# Schematic.net
KiCad netlist of a schematic drawn in Altium Designer
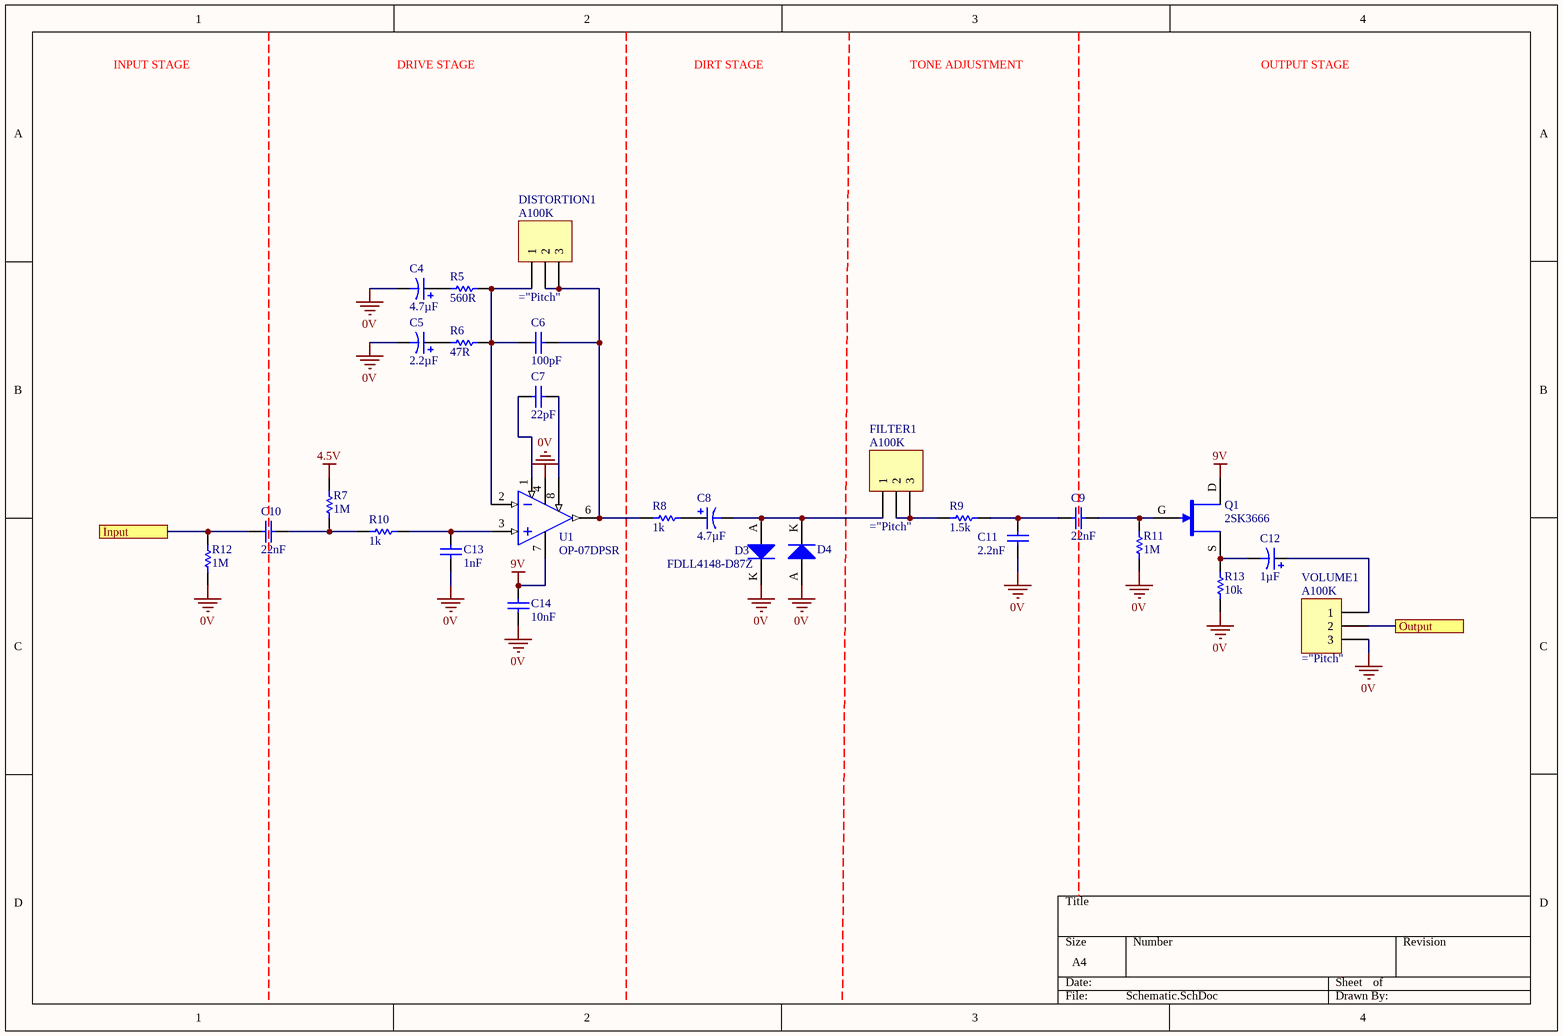
[diagram p0: Schematic.SchDoc]

(export (version "E")
  (design (tool "Eeschema 10.0.6"))
  (components
    (comp (ref "C4")
      (value "~")
      (footprint "1206")
      (fields
        (field (name "PART NUMBER") "TAJA475K025RNJ")
        (field (name "TOLERANCE") "±10%")
        (field (name "MANUFACTURER") "AVX Corporation")
      )
      (libsource (lib "ts_20-standard-library") (part "Capacitor (Polarised)"))
    )
    (comp (ref "C5")
      (value "~")
      (footprint "1206")
      (fields
        (field (name "PART NUMBER") "TAJA225K025RNJ")
        (field (name "TOLERANCE") "±10%")
        (field (name "MANUFACTURER") "AVX Corporation")
      )
      (libsource (lib "ts_20-standard-library") (part "Capacitor (Polarised)"))
    )
    (comp (ref "C6")
      (value "100pF")
      (footprint "0805")
      (fields
        (field (name "PART NUMBER") "GCM2165C1H101JA16D")
        (field (name "TOLERANCE") "±5%")
        (field (name "MANUFACTURER") "muRata")
      )
      (libsource (lib "ts_20-standard-library") (part "Capacitor"))
    )
    (comp (ref "C7")
      (value "22pF")
      (footprint "0805")
      (fields
        (field (name "PART NUMBER") "GRM21A5C2E220JW01D")
        (field (name "TOLERANCE") "±5%")
        (field (name "MANUFACTURER") "muRata")
      )
      (libsource (lib "ts_20-standard-library") (part "Capacitor"))
    )
    (comp (ref "C8")
      (value "~")
      (footprint "1206")
      (fields
        (field (name "PART NUMBER") "TAJA475K025RNJ")
        (field (name "TOLERANCE") "±10%")
        (field (name "MANUFACTURER") "AVX Corporation")
      )
      (libsource (lib "ts_20-standard-library") (part "Capacitor (Polarised)"))
    )
    (comp (ref "C9")
      (value "22nF")
      (footprint "0805")
      (fields
        (field (name "PART NUMBER") "GCM21B5C1H223JA16L")
        (field (name "TOLERANCE") "±5%")
        (field (name "MANUFACTURER") "muRata")
      )
      (libsource (lib "ts_20-standard-library") (part "Capacitor"))
    )
    (comp (ref "C10")
      (value "22nF")
      (footprint "0805")
      (fields
        (field (name "PART NUMBER") "GCM21B5C1H223JA16L")
        (field (name "TOLERANCE") "±5%")
        (field (name "MANUFACTURER") "muRata")
      )
      (libsource (lib "ts_20-standard-library") (part "Capacitor"))
    )
    (comp (ref "C11")
      (value "2.2nF")
      (footprint "0805")
      (fields
        (field (name "PART NUMBER") "GCM2165C1H222JA16D")
        (field (name "TOLERANCE") "±5%")
        (field (name "MANUFACTURER") "muRata")
      )
      (libsource (lib "ts_20-standard-library") (part "Capacitor"))
    )
    (comp (ref "C12")
      (value "~")
      (footprint "1206")
      (fields
        (field (name "PART NUMBER") "TAJA105K025RNJ")
        (field (name "TOLERANCE") "±10%")
        (field (name "MANUFACTURER") "AVX Corporation")
      )
      (libsource (lib "ts_20-standard-library") (part "Capacitor (Polarised)"))
    )
    (comp (ref "C13")
      (value "1nF")
      (footprint "0805")
      (fields
        (field (name "PART NUMBER") "GCM2165C1H102JA16D")
        (field (name "TOLERANCE") "±5%")
        (field (name "MANUFACTURER") "muRata")
      )
      (libsource (lib "ts_20-standard-library") (part "Capacitor"))
    )
    (comp (ref "C14")
      (value "10nF")
      (footprint "0805")
      (fields
        (field (name "PART NUMBER") "GCM2195C1H103JA16D")
        (field (name "TOLERANCE") "±5%")
        (field (name "MANUFACTURER") "muRata")
      )
      (libsource (lib "ts_20-standard-library") (part "Capacitor"))
    )
    (comp (ref "D3")
      (value "FDLL4148-D87Z")
      (footprint "SOD-80 Diode")
      (description "DIODE GEN PURP 100V 200MA SOD80")
      (fields
        (field (name "MANUFACTURER") "On Semiconductor")
        (field (name "DIGIKEY PART NUMBER") "FDLL4148-D87ZCT-ND")
      )
      (libsource (lib "ts_20-standard-library") (part "Diode"))
    )
    (comp (ref "D4")
      (value "FDLL4148-D87Z")
      (footprint "SOD-80 Diode")
      (description "DIODE GEN PURP 100V 200MA SOD80")
      (fields
        (field (name "MANUFACTURER") "On Semiconductor")
        (field (name "DIGIKEY PART NUMBER") "FDLL4148-D87ZCT-ND")
      )
      (libsource (lib "ts_20-standard-library") (part "Diode"))
    )
    (comp (ref "DISTORTION1")
      (value "~")
      (footprint "TH 2.54mm Header 1x3")
      (fields (field (name "PART NUMBER") "A100K POT") (field (name "RESISTANCE") "A100K"))
      (libsource (lib "ts_20-standard-connectors") (part "Header 1x3"))
    )
    (comp (ref "FILTER1")
      (value "~")
      (footprint "TH 2.54mm Header 1x3")
      (fields (field (name "PART NUMBER") "A100K POT") (field (name "RESISTANCE") "A100K"))
      (libsource (lib "ts_20-standard-connectors") (part "Header 1x3"))
    )
    (comp (ref "Q1")
      (value "2SK3666")
      (footprint "ON SOT-23 JFET")
      (description "JFET N-Channel 10mA 200mW Surface Mount 3-CP")
      (fields
        (field (name "MANUFACTURER") "ON Semiconductor")
        (field (name "DIGIKEY PART NUMBER") "869-1107-1-ND")
        (field (name "PUBLISHER") "Altium Limited")
      )
      (libsource (lib "ts_20-standard-library") (part "JFET-N"))
    )
    (comp (ref "R5")
      (value "560R")
      (footprint "0805")
      (fields
        (field (name "PART NUMBER") "RC0805FR07560RL")
        (field (name "MANUFACTURER") "YAGEO")
        (field (name "TOLERANCE") "0.01")
      )
      (libsource (lib "ts_20-standard-library") (part "Resistor"))
    )
    (comp (ref "R6")
      (value "47R")
      (footprint "0805")
      (fields
        (field (name "PART NUMBER") "RC0805FR0747RL")
        (field (name "MANUFACTURER") "YAGEO")
        (field (name "TOLERANCE") "0.01")
      )
      (libsource (lib "ts_20-standard-library") (part "Resistor"))
    )
    (comp (ref "R7")
      (value "1M")
      (footprint "0805")
      (fields
        (field (name "PART NUMBER") "RC0805FR071ML")
        (field (name "MANUFACTURER") "YAGEO")
        (field (name "TOLERANCE") "0.01")
      )
      (libsource (lib "ts_20-standard-library") (part "Resistor"))
    )
    (comp (ref "R8")
      (value "1k")
      (footprint "0805")
      (fields
        (field (name "PART NUMBER") "RC0805FR071KL")
        (field (name "MANUFACTURER") "YAGEO")
        (field (name "TOLERANCE") "0.01")
      )
      (libsource (lib "ts_20-standard-library") (part "Resistor"))
    )
    (comp (ref "R9")
      (value "1.5k")
      (footprint "0805")
      (fields
        (field (name "PART NUMBER") "RC0805FR071K5L")
        (field (name "MANUFACTURER") "YAGEO")
        (field (name "TOLERANCE") "0.01")
      )
      (libsource (lib "ts_20-standard-library") (part "Resistor"))
    )
    (comp (ref "R10")
      (value "1k")
      (footprint "0805")
      (fields
        (field (name "PART NUMBER") "RC0805FR071KL")
        (field (name "MANUFACTURER") "YAGEO")
        (field (name "TOLERANCE") "0.01")
      )
      (libsource (lib "ts_20-standard-library") (part "Resistor"))
    )
    (comp (ref "R11")
      (value "1M")
      (footprint "0805")
      (fields
        (field (name "PART NUMBER") "RC0805FR071ML")
        (field (name "MANUFACTURER") "YAGEO")
        (field (name "TOLERANCE") "0.01")
      )
      (libsource (lib "ts_20-standard-library") (part "Resistor"))
    )
    (comp (ref "R12")
      (value "1M")
      (footprint "0805")
      (fields
        (field (name "PART NUMBER") "RC0805FR071ML")
        (field (name "MANUFACTURER") "YAGEO")
        (field (name "TOLERANCE") "0.01")
      )
      (libsource (lib "ts_20-standard-library") (part "Resistor"))
    )
    (comp (ref "R13")
      (value "10k")
      (footprint "0805")
      (fields
        (field (name "PART NUMBER") "RC0805FR0710KL")
        (field (name "MANUFACTURER") "YAGEO")
        (field (name "TOLERANCE") "0.01")
      )
      (libsource (lib "ts_20-standard-library") (part "Resistor"))
    )
    (comp (ref "U1")
      (value "OP-07DPSR")
      (footprint "TI 8-SOIC")
      (description "General Purpose Amplifier 1 Circuit 8-SO")
      (fields
        (field (name "MANUFACTURER") "Texas Instruments")
        (field (name "DIGIKEY PART NUMBER") "296-14171-2-ND")
      )
      (libsource (lib "ts_20-standard-library") (part "OP07DP"))
    )
    (comp (ref "VOLUME1")
      (value "~")
      (footprint "TH 2.54mm Header 1x3")
      (fields (field (name "PART NUMBER") "A100K POT") (field (name "RESISTANCE") "A100K"))
      (libsource (lib "") (part "Header 1x3_1"))
    )
  )
  (nets
    (net (code "1") (name "/Input") (class "Default")
      (node (ref "C10") (pin "1") (pinfunction "1_1") (pintype "passive"))
      (node (ref "R12") (pin "2") (pinfunction "2_2") (pintype "passive"))
    )
    (net (code "2") (name "/Output") (class "Default")
      (node (ref "VOLUME1") (pin "2") (pinfunction "2_2") (pintype "passive"))
    )
    (net (code "3") (name "0V") (class "Default")
      (node (ref "C11") (pin "1") (pinfunction "1_1") (pintype "passive"))
      (node (ref "C13") (pin "1") (pinfunction "1_1") (pintype "passive"))
      (node (ref "C14") (pin "1") (pinfunction "1_1") (pintype "passive"))
      (node (ref "C4") (pin "1") (pinfunction "1_1") (pintype "passive"))
      (node (ref "C5") (pin "1") (pinfunction "1_1") (pintype "passive"))
      (node (ref "D3") (pin "K") (pinfunction "K_K") (pintype "passive"))
      (node (ref "D4") (pin "A") (pinfunction "A_A") (pintype "passive"))
      (node (ref "R11") (pin "1") (pinfunction "1_1") (pintype "passive"))
      (node (ref "R12") (pin "1") (pinfunction "1_1") (pintype "passive"))
      (node (ref "R13") (pin "1") (pinfunction "1_1") (pintype "passive"))
      (node (ref "U1") (pin "4") (pinfunction "VCC-_4") (pintype "power_in"))
      (node (ref "VOLUME1") (pin "3") (pinfunction "3_3") (pintype "passive"))
    )
    (net (code "4") (name "4.5V") (class "Default")
      (node (ref "R7") (pin "2") (pinfunction "2_2") (pintype "passive"))
    )
    (net (code "5") (name "9V") (class "Default")
      (node (ref "C14") (pin "2") (pinfunction "2_2") (pintype "passive"))
      (node (ref "Q1") (pin "D") (pinfunction "D_D") (pintype "passive"))
      (node (ref "U1") (pin "7") (pinfunction "VCC+_7") (pintype "power_in"))
    )
    (net (code "6") (name "Net-(C4-Pad2)") (class "Default")
      (node (ref "C4") (pin "2") (pinfunction "2_2") (pintype "passive"))
      (node (ref "R5") (pin "1") (pinfunction "1_1") (pintype "passive"))
    )
    (net (code "7") (name "Net-(C5-Pad2)") (class "Default")
      (node (ref "C5") (pin "2") (pinfunction "2_2") (pintype "passive"))
      (node (ref "R6") (pin "1") (pinfunction "1_1") (pintype "passive"))
    )
    (net (code "8") (name "Net-(C8-Pad1)") (class "Default")
      (node (ref "C8") (pin "1") (pinfunction "1_1") (pintype "passive"))
      (node (ref "D3") (pin "A") (pinfunction "A_A") (pintype "passive"))
      (node (ref "D4") (pin "K") (pinfunction "K_K") (pintype "passive"))
      (node (ref "FILTER1") (pin "1") (pinfunction "1_1") (pintype "passive"))
    )
    (net (code "9") (name "Net-(C8-Pad2)") (class "Default")
      (node (ref "C8") (pin "2") (pinfunction "2_2") (pintype "passive"))
      (node (ref "R8") (pin "2") (pinfunction "2_2") (pintype "passive"))
    )
    (net (code "10") (name "Net-(C9-Pad2)") (class "Default")
      (node (ref "C9") (pin "2") (pinfunction "2_2") (pintype "passive"))
      (node (ref "Q1") (pin "G") (pinfunction "G_G") (pintype "passive"))
      (node (ref "R11") (pin "2") (pinfunction "2_2") (pintype "passive"))
    )
    (net (code "11") (name "Net-(C10-Pad2)") (class "Default")
      (node (ref "C10") (pin "2") (pinfunction "2_2") (pintype "passive"))
      (node (ref "R10") (pin "1") (pinfunction "1_1") (pintype "passive"))
      (node (ref "R7") (pin "1") (pinfunction "1_1") (pintype "passive"))
    )
    (net (code "12") (name "Net-(C11-Pad2)") (class "Default")
      (node (ref "C11") (pin "2") (pinfunction "2_2") (pintype "passive"))
      (node (ref "C9") (pin "1") (pinfunction "1_1") (pintype "passive"))
      (node (ref "R9") (pin "2") (pinfunction "2_2") (pintype "passive"))
    )
    (net (code "13") (name "Net-(C12-Pad1)") (class "Default")
      (node (ref "C12") (pin "1") (pinfunction "1_1") (pintype "passive"))
      (node (ref "Q1") (pin "S") (pinfunction "S_S") (pintype "passive"))
      (node (ref "R13") (pin "2") (pinfunction "2_2") (pintype "passive"))
    )
    (net (code "14") (name "Net-(C12-Pad2)") (class "Default")
      (node (ref "C12") (pin "2") (pinfunction "2_2") (pintype "passive"))
      (node (ref "VOLUME1") (pin "1") (pinfunction "1_1") (pintype "passive"))
    )
    (net (code "15") (name "Net-(FILTER1-Pad2)") (class "Default")
      (node (ref "FILTER1") (pin "2") (pinfunction "2_2") (pintype "passive"))
      (node (ref "FILTER1") (pin "3") (pinfunction "3_3") (pintype "passive"))
      (node (ref "R9") (pin "1") (pinfunction "1_1") (pintype "passive"))
    )
    (net (code "16") (name "Net-(U1-IN+)") (class "Default")
      (node (ref "C13") (pin "2") (pinfunction "2_2") (pintype "passive"))
      (node (ref "R10") (pin "2") (pinfunction "2_2") (pintype "passive"))
      (node (ref "U1") (pin "3") (pinfunction "IN+_3") (pintype "input"))
    )
    (net (code "17") (name "Net-(U1-IN-)") (class "Default")
      (node (ref "C6") (pin "1") (pinfunction "1_1") (pintype "passive"))
      (node (ref "DISTORTION1") (pin "1") (pinfunction "1_1") (pintype "passive"))
      (node (ref "R5") (pin "2") (pinfunction "2_2") (pintype "passive"))
      (node (ref "R6") (pin "2") (pinfunction "2_2") (pintype "passive"))
      (node (ref "U1") (pin "2") (pinfunction "IN-_2") (pintype "input"))
    )
    (net (code "18") (name "Net-(U1-OFFSET_N1)") (class "Default")
      (node (ref "C7") (pin "1") (pinfunction "1_1") (pintype "passive"))
      (node (ref "U1") (pin "1") (pinfunction "OFFSET_N1_1") (pintype "input"))
    )
    (net (code "19") (name "Net-(U1-OFFSET_N2)") (class "Default")
      (node (ref "C7") (pin "2") (pinfunction "2_2") (pintype "passive"))
      (node (ref "U1") (pin "8") (pinfunction "OFFSET_N2_8") (pintype "input"))
    )
    (net (code "20") (name "Net-(U1-OUT)") (class "Default")
      (node (ref "C6") (pin "2") (pinfunction "2_2") (pintype "passive"))
      (node (ref "DISTORTION1") (pin "2") (pinfunction "2_2") (pintype "passive"))
      (node (ref "DISTORTION1") (pin "3") (pinfunction "3_3") (pintype "passive"))
      (node (ref "R8") (pin "1") (pinfunction "1_1") (pintype "passive"))
      (node (ref "U1") (pin "6") (pinfunction "OUT_6") (pintype "output"))
    )
  )
)
